# display.net
KiCad netlist of a schematic drawn in EAGLE
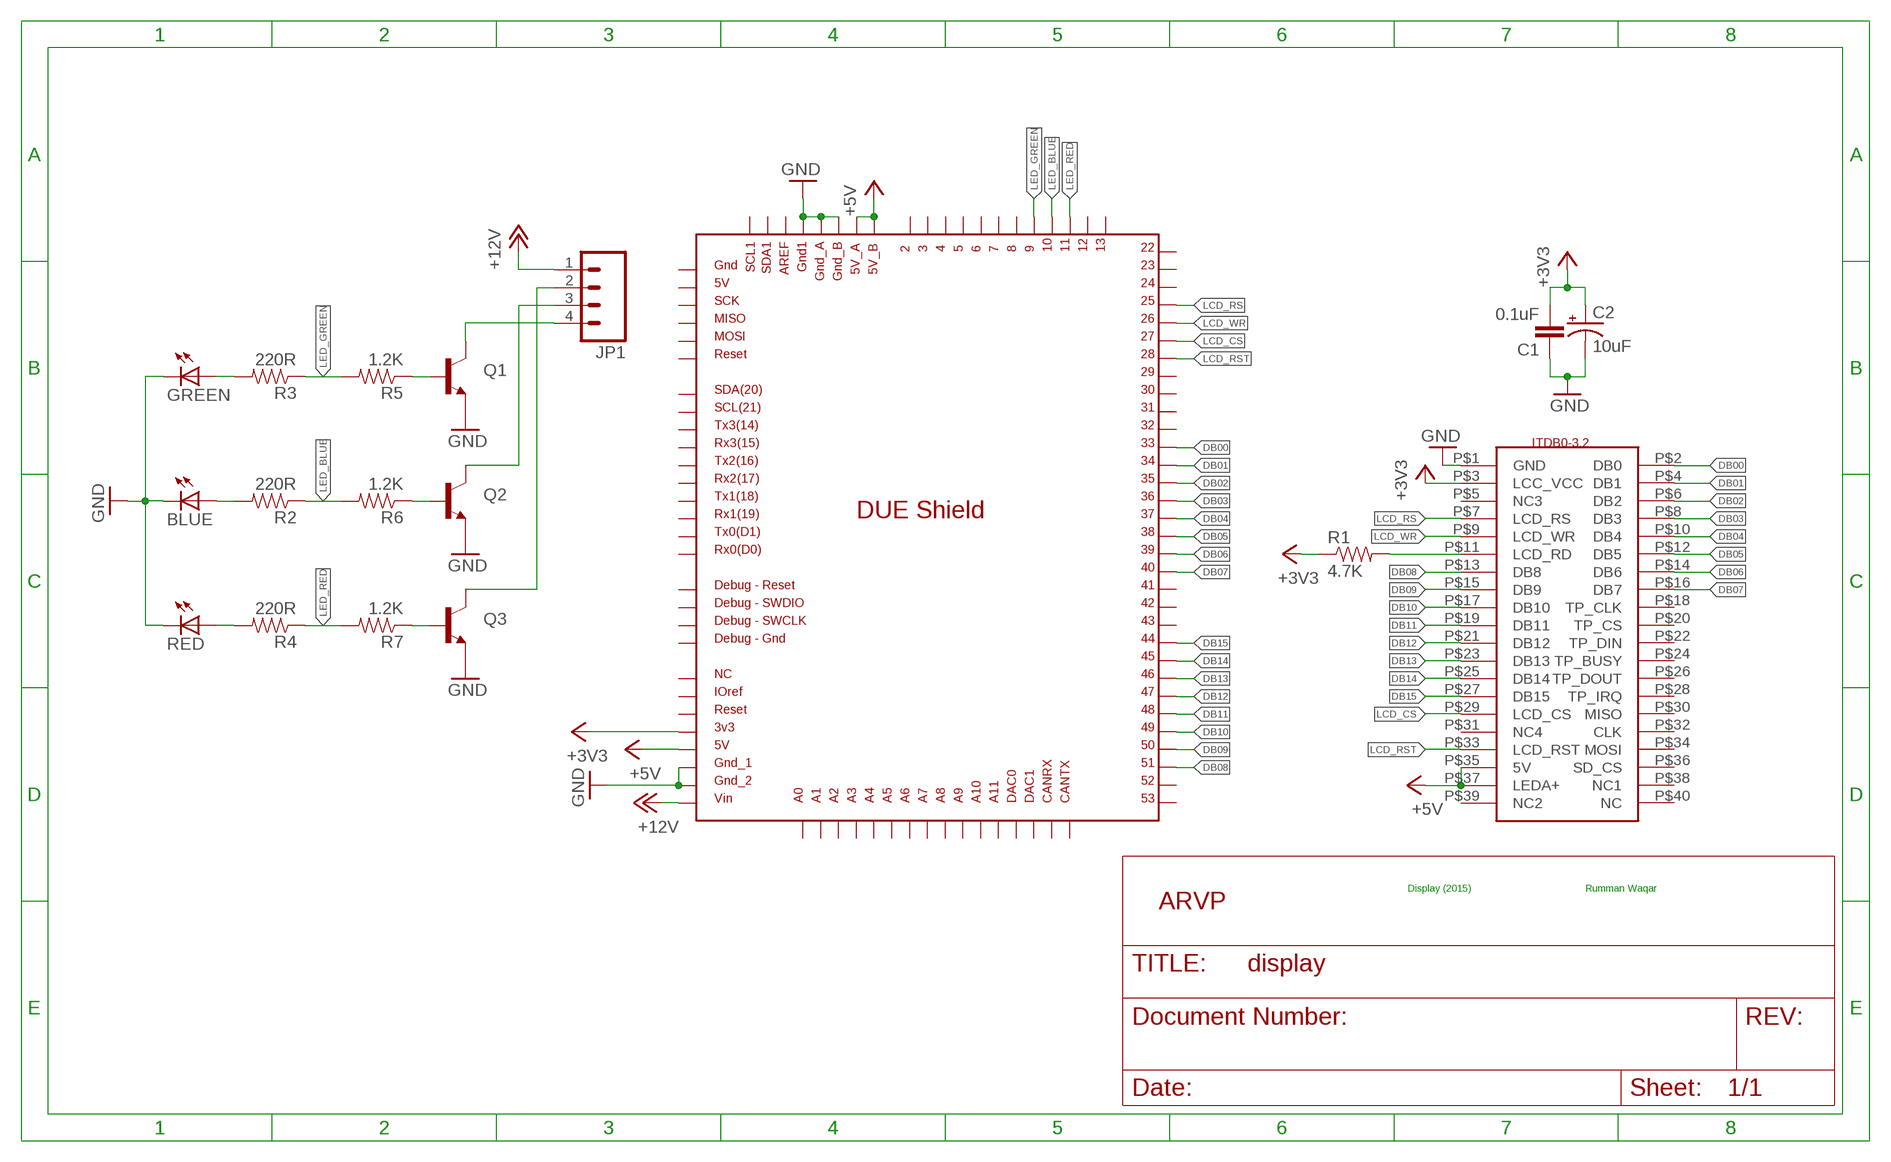
[diagram p0: schematic, sheet 1]

(export (version "E")
  (design (tool "Eeschema 10.0.6"))
  (components
    (comp (ref "BLUE")
      (value "LED1206")
      (footprint "eagle-import:LED-1206")
      (libsource (lib "eagle-import") (part "LED1206"))
    )
    (comp (ref "C1")
      (value "0.1uF")
      (footprint "eagle-import:1206")
      (libsource (lib "eagle-import") (part "CAP1206"))
    )
    (comp (ref "C2")
      (value "10uF")
      (footprint "eagle-import:EIA3216")
      (libsource (lib "eagle-import") (part "CAP_POL1206"))
    )
    (comp (ref "GREEN")
      (value "LED1206")
      (footprint "eagle-import:LED-1206")
      (libsource (lib "eagle-import") (part "LED1206"))
    )
    (comp (ref "JP1")
      (value "M04POLAR")
      (footprint "eagle-import:MOLEX-1X4")
      (libsource (lib "eagle-import") (part "M04POLAR"))
    )
    (comp (ref "Q1")
      (value "TRANSISTOR_NPN\"")
      (footprint "eagle-import:SOT223")
      (libsource (lib "eagle-import") (part "TRANSISTOR_NPN{dblquote}"))
    )
    (comp (ref "Q2")
      (value "TRANSISTOR_NPN\"")
      (footprint "eagle-import:SOT223")
      (libsource (lib "eagle-import") (part "TRANSISTOR_NPN{dblquote}"))
    )
    (comp (ref "Q3")
      (value "TRANSISTOR_NPN\"")
      (footprint "eagle-import:SOT223")
      (libsource (lib "eagle-import") (part "TRANSISTOR_NPN{dblquote}"))
    )
    (comp (ref "R1")
      (value "4.7K")
      (footprint "eagle-import:0805")
      (libsource (lib "eagle-import") (part "RESISTOR0805-RES"))
    )
    (comp (ref "R2")
      (value "220R")
      (footprint "eagle-import:1206")
      (libsource (lib "eagle-import") (part "RESISTOR1206"))
    )
    (comp (ref "R3")
      (value "220R")
      (footprint "eagle-import:1206")
      (libsource (lib "eagle-import") (part "RESISTOR1206"))
    )
    (comp (ref "R4")
      (value "220R")
      (footprint "eagle-import:1206")
      (libsource (lib "eagle-import") (part "RESISTOR1206"))
    )
    (comp (ref "R5")
      (value "1.2K")
      (footprint "eagle-import:1206")
      (libsource (lib "eagle-import") (part "RESISTOR1206"))
    )
    (comp (ref "R6")
      (value "1.2K")
      (footprint "eagle-import:1206")
      (libsource (lib "eagle-import") (part "RESISTOR1206"))
    )
    (comp (ref "R7")
      (value "1.2K")
      (footprint "eagle-import:1206")
      (libsource (lib "eagle-import") (part "RESISTOR1206"))
    )
    (comp (ref "RED")
      (value "LED1206")
      (footprint "eagle-import:LED-1206")
      (libsource (lib "eagle-import") (part "LED1206"))
    )
    (comp (ref "U$1")
      (value "DUE(NORMAL)")
      (footprint "eagle-import:DUE(NORMAL)")
      (libsource (lib "eagle-import") (part "DUE(NORMAL)"))
    )
    (comp (ref "U$2")
      (value "ARVP_LOGO")
      (footprint "eagle-import:ARVP")
      (libsource (lib "eagle-import") (part "ARVP_LOGO"))
    )
    (comp (ref "U$3")
      (value "ITDB0-3.2")
      (footprint "eagle-import:ITDB02-3.2")
      (libsource (lib "eagle-import") (part "ITDB0-3.2"))
    )
  )
  (nets
    (net (code "1") (name "+3V3") (class "Default")
      (node (ref "C1") (pin "2") (pinfunction "2_2") (pintype "passive"))
      (node (ref "C2") (pin "A") (pinfunction "+_A") (pintype "passive"))
      (node (ref "R1") (pin "1") (pinfunction "1_1") (pintype "passive"))
      (node (ref "U$1") (pin "3V3") (pinfunction "3V3_3V3") (pintype "bidirectional"))
      (node (ref "U$3") (pin "P$3") (pinfunction "LCC_VCC_P$3") (pintype "power_in"))
    )
    (net (code "2") (name "+5V") (class "Default")
      (node (ref "U$1") (pin "5V") (pinfunction "5V_5V") (pintype "bidirectional"))
      (node (ref "U$1") (pin "5V_A") (pinfunction "5V_A_5V_A") (pintype "bidirectional"))
      (node (ref "U$1") (pin "5V_B") (pinfunction "5V_B_5V_B") (pintype "bidirectional"))
      (node (ref "U$3") (pin "P$35") (pinfunction "5V_P$35") (pintype "power_in"))
      (node (ref "U$3") (pin "P$37") (pinfunction "LEDA+_P$37") (pintype "power_in"))
    )
    (net (code "3") (name "+12V") (class "Default")
      (node (ref "JP1") (pin "1") (pinfunction "1_1") (pintype "passive"))
      (node (ref "U$1") (pin "VIN") (pinfunction "VIN_VIN") (pintype "bidirectional"))
    )
    (net (code "4") (name "DB00") (class "Default")
      (node (ref "U$1") (pin "33") (pinfunction "33_33") (pintype "bidirectional"))
      (node (ref "U$3") (pin "P$2") (pinfunction "DB0_P$2") (pintype "bidirectional"))
    )
    (net (code "5") (name "DB01") (class "Default")
      (node (ref "U$1") (pin "34") (pinfunction "34_34") (pintype "bidirectional"))
      (node (ref "U$3") (pin "P$4") (pinfunction "DB1_P$4") (pintype "bidirectional"))
    )
    (net (code "6") (name "DB02") (class "Default")
      (node (ref "U$1") (pin "35") (pinfunction "35_35") (pintype "bidirectional"))
      (node (ref "U$3") (pin "P$6") (pinfunction "DB2_P$6") (pintype "bidirectional"))
    )
    (net (code "7") (name "DB03") (class "Default")
      (node (ref "U$1") (pin "36") (pinfunction "36_36") (pintype "bidirectional"))
      (node (ref "U$3") (pin "P$8") (pinfunction "DB3_P$8") (pintype "bidirectional"))
    )
    (net (code "8") (name "DB04") (class "Default")
      (node (ref "U$1") (pin "37") (pinfunction "37_37") (pintype "bidirectional"))
      (node (ref "U$3") (pin "P$10") (pinfunction "DB4_P$10") (pintype "bidirectional"))
    )
    (net (code "9") (name "DB05") (class "Default")
      (node (ref "U$1") (pin "38") (pinfunction "38_38") (pintype "bidirectional"))
      (node (ref "U$3") (pin "P$12") (pinfunction "DB5_P$12") (pintype "bidirectional"))
    )
    (net (code "10") (name "DB06") (class "Default")
      (node (ref "U$1") (pin "39") (pinfunction "39_39") (pintype "bidirectional"))
      (node (ref "U$3") (pin "P$14") (pinfunction "DB6_P$14") (pintype "bidirectional"))
    )
    (net (code "11") (name "DB07") (class "Default")
      (node (ref "U$1") (pin "40") (pinfunction "40_40") (pintype "bidirectional"))
      (node (ref "U$3") (pin "P$16") (pinfunction "DB7_P$16") (pintype "bidirectional"))
    )
    (net (code "12") (name "DB08") (class "Default")
      (node (ref "U$1") (pin "51") (pinfunction "51_51") (pintype "bidirectional"))
      (node (ref "U$3") (pin "P$13") (pinfunction "DB8_P$13") (pintype "bidirectional"))
    )
    (net (code "13") (name "DB09") (class "Default")
      (node (ref "U$1") (pin "50") (pinfunction "50_50") (pintype "bidirectional"))
      (node (ref "U$3") (pin "P$15") (pinfunction "DB9_P$15") (pintype "bidirectional"))
    )
    (net (code "14") (name "DB10") (class "Default")
      (node (ref "U$1") (pin "49") (pinfunction "49_49") (pintype "bidirectional"))
      (node (ref "U$3") (pin "P$17") (pinfunction "DB10_P$17") (pintype "bidirectional"))
    )
    (net (code "15") (name "DB11") (class "Default")
      (node (ref "U$1") (pin "48") (pinfunction "48_48") (pintype "bidirectional"))
      (node (ref "U$3") (pin "P$19") (pinfunction "DB11_P$19") (pintype "bidirectional"))
    )
    (net (code "16") (name "DB12") (class "Default")
      (node (ref "U$1") (pin "47") (pinfunction "47_47") (pintype "bidirectional"))
      (node (ref "U$3") (pin "P$21") (pinfunction "DB12_P$21") (pintype "bidirectional"))
    )
    (net (code "17") (name "DB13") (class "Default")
      (node (ref "U$1") (pin "46") (pinfunction "46_46") (pintype "bidirectional"))
      (node (ref "U$3") (pin "P$23") (pinfunction "DB13_P$23") (pintype "bidirectional"))
    )
    (net (code "18") (name "DB14") (class "Default")
      (node (ref "U$1") (pin "45") (pinfunction "45_45") (pintype "bidirectional"))
      (node (ref "U$3") (pin "P$25") (pinfunction "DB14_P$25") (pintype "bidirectional"))
    )
    (net (code "19") (name "DB15") (class "Default")
      (node (ref "U$1") (pin "44") (pinfunction "44_44") (pintype "bidirectional"))
      (node (ref "U$3") (pin "P$27") (pinfunction "DB15_P$27") (pintype "bidirectional"))
    )
    (net (code "20") (name "GND") (class "Default")
      (node (ref "BLUE") (pin "C") (pinfunction "C_C") (pintype "passive"))
      (node (ref "C1") (pin "1") (pinfunction "1_1") (pintype "passive"))
      (node (ref "C2") (pin "C") (pinfunction "-_C") (pintype "passive"))
      (node (ref "GREEN") (pin "C") (pinfunction "C_C") (pintype "passive"))
      (node (ref "Q1") (pin "3") (pinfunction "E_3") (pintype "passive"))
      (node (ref "Q2") (pin "3") (pinfunction "E_3") (pintype "passive"))
      (node (ref "Q3") (pin "3") (pinfunction "E_3") (pintype "passive"))
      (node (ref "RED") (pin "C") (pinfunction "C_C") (pintype "passive"))
      (node (ref "U$1") (pin "GND1") (pinfunction "GND1_GND1") (pintype "bidirectional"))
      (node (ref "U$1") (pin "GND_1") (pinfunction "GND_1_GND_1") (pintype "bidirectional"))
      (node (ref "U$1") (pin "GND_2") (pinfunction "GND_2_GND_2") (pintype "bidirectional"))
      (node (ref "U$1") (pin "GND_A") (pinfunction "GND_A_GND_A") (pintype "bidirectional"))
      (node (ref "U$1") (pin "GND_B") (pinfunction "GND_B_GND_B") (pintype "bidirectional"))
      (node (ref "U$3") (pin "P$1") (pinfunction "GND_P$1") (pintype "power_in"))
    )
    (net (code "21") (name "LCD_CS") (class "Default")
      (node (ref "U$1") (pin "27") (pinfunction "27_27") (pintype "bidirectional"))
      (node (ref "U$3") (pin "P$29") (pinfunction "LCD_CS_P$29") (pintype "bidirectional"))
    )
    (net (code "22") (name "LCD_RS") (class "Default")
      (node (ref "U$1") (pin "25") (pinfunction "25_25") (pintype "bidirectional"))
      (node (ref "U$3") (pin "P$7") (pinfunction "LCD_RS_P$7") (pintype "bidirectional"))
    )
    (net (code "23") (name "LCD_RST") (class "Default")
      (node (ref "U$1") (pin "28") (pinfunction "28_28") (pintype "bidirectional"))
      (node (ref "U$3") (pin "P$33") (pinfunction "LCD_RST_P$33") (pintype "bidirectional"))
    )
    (net (code "24") (name "LCD_WR") (class "Default")
      (node (ref "U$1") (pin "26") (pinfunction "26_26") (pintype "bidirectional"))
      (node (ref "U$3") (pin "P$9") (pinfunction "LCD_WR_P$9") (pintype "bidirectional"))
    )
    (net (code "25") (name "LED_BLUE") (class "Default")
      (node (ref "R2") (pin "1") (pinfunction "1_1") (pintype "passive"))
      (node (ref "R6") (pin "2") (pinfunction "2_2") (pintype "passive"))
      (node (ref "U$1") (pin "10") (pinfunction "10_10") (pintype "bidirectional"))
    )
    (net (code "26") (name "LED_GREEN") (class "Default")
      (node (ref "R3") (pin "1") (pinfunction "1_1") (pintype "passive"))
      (node (ref "R5") (pin "2") (pinfunction "2_2") (pintype "passive"))
      (node (ref "U$1") (pin "9") (pinfunction "9_9") (pintype "bidirectional"))
    )
    (net (code "27") (name "LED_RED") (class "Default")
      (node (ref "R4") (pin "1") (pinfunction "1_1") (pintype "passive"))
      (node (ref "R7") (pin "2") (pinfunction "2_2") (pintype "passive"))
      (node (ref "U$1") (pin "11") (pinfunction "11_11") (pintype "bidirectional"))
    )
    (net (code "28") (name "Net-(BLUE-PadA)") (class "Default")
      (node (ref "BLUE") (pin "A") (pinfunction "A_A") (pintype "passive"))
      (node (ref "R2") (pin "2") (pinfunction "2_2") (pintype "passive"))
    )
    (net (code "29") (name "Net-(GREEN-PadA)") (class "Default")
      (node (ref "GREEN") (pin "A") (pinfunction "A_A") (pintype "passive"))
      (node (ref "R3") (pin "2") (pinfunction "2_2") (pintype "passive"))
    )
    (net (code "30") (name "Net-(Q1-B)") (class "Default")
      (node (ref "Q1") (pin "1") (pinfunction "B_1") (pintype "passive"))
      (node (ref "R5") (pin "1") (pinfunction "1_1") (pintype "passive"))
    )
    (net (code "31") (name "Net-(Q1-C)") (class "Default")
      (node (ref "JP1") (pin "4") (pinfunction "4_4") (pintype "passive"))
      (node (ref "Q1") (pin "2") (pinfunction "C_2") (pintype "passive"))
    )
    (net (code "32") (name "Net-(Q2-B)") (class "Default")
      (node (ref "Q2") (pin "1") (pinfunction "B_1") (pintype "passive"))
      (node (ref "R6") (pin "1") (pinfunction "1_1") (pintype "passive"))
    )
    (net (code "33") (name "Net-(Q2-C)") (class "Default")
      (node (ref "JP1") (pin "3") (pinfunction "3_3") (pintype "passive"))
      (node (ref "Q2") (pin "2") (pinfunction "C_2") (pintype "passive"))
    )
    (net (code "34") (name "Net-(Q3-B)") (class "Default")
      (node (ref "Q3") (pin "1") (pinfunction "B_1") (pintype "passive"))
      (node (ref "R7") (pin "1") (pinfunction "1_1") (pintype "passive"))
    )
    (net (code "35") (name "Net-(Q3-C)") (class "Default")
      (node (ref "JP1") (pin "2") (pinfunction "2_2") (pintype "passive"))
      (node (ref "Q3") (pin "2") (pinfunction "C_2") (pintype "passive"))
    )
    (net (code "36") (name "Net-(R4-Pad2)") (class "Default")
      (node (ref "R4") (pin "2") (pinfunction "2_2") (pintype "passive"))
      (node (ref "RED") (pin "A") (pinfunction "A_A") (pintype "passive"))
    )
    (net (code "37") (name "Net-(U$3-LCD_RD)") (class "Default")
      (node (ref "R1") (pin "2") (pinfunction "2_2") (pintype "passive"))
      (node (ref "U$3") (pin "P$11") (pinfunction "LCD_RD_P$11") (pintype "bidirectional"))
    )
    (net (code "38") (name "unconnected-(U$1-Pad2)") (class "Default")
      (node (ref "U$1") (pin "2") (pinfunction "2_2") (pintype "bidirectional"))
    )
    (net (code "39") (name "unconnected-(U$1-Pad3)") (class "Default")
      (node (ref "U$1") (pin "3") (pinfunction "3_3") (pintype "bidirectional"))
    )
    (net (code "40") (name "unconnected-(U$1-Pad4)") (class "Default")
      (node (ref "U$1") (pin "4") (pinfunction "4_4") (pintype "bidirectional"))
    )
    (net (code "41") (name "unconnected-(U$1-Pad5)") (class "Default")
      (node (ref "U$1") (pin "5") (pinfunction "5_5") (pintype "bidirectional"))
    )
    (net (code "42") (name "unconnected-(U$1-Pad5V_ICSP)") (class "Default")
      (node (ref "U$1") (pin "5V_ICSP") (pinfunction "5V_ICSP_5V_ICSP") (pintype "bidirectional"))
    )
    (net (code "43") (name "unconnected-(U$1-Pad6)") (class "Default")
      (node (ref "U$1") (pin "6") (pinfunction "6_6") (pintype "bidirectional"))
    )
    (net (code "44") (name "unconnected-(U$1-Pad7)") (class "Default")
      (node (ref "U$1") (pin "7") (pinfunction "7_7") (pintype "bidirectional"))
    )
    (net (code "45") (name "unconnected-(U$1-Pad8)") (class "Default")
      (node (ref "U$1") (pin "8") (pinfunction "8_8") (pintype "bidirectional"))
    )
    (net (code "46") (name "unconnected-(U$1-Pad12)") (class "Default")
      (node (ref "U$1") (pin "12") (pinfunction "12_12") (pintype "bidirectional"))
    )
    (net (code "47") (name "unconnected-(U$1-Pad13)") (class "Default")
      (node (ref "U$1") (pin "13") (pinfunction "13_13") (pintype "bidirectional"))
    )
    (net (code "48") (name "unconnected-(U$1-Pad22)") (class "Default")
      (node (ref "U$1") (pin "22") (pinfunction "22_22") (pintype "bidirectional"))
    )
    (net (code "49") (name "unconnected-(U$1-Pad23)") (class "Default")
      (node (ref "U$1") (pin "23") (pinfunction "23_23") (pintype "bidirectional"))
    )
    (net (code "50") (name "unconnected-(U$1-Pad24)") (class "Default")
      (node (ref "U$1") (pin "24") (pinfunction "24_24") (pintype "bidirectional"))
    )
    (net (code "51") (name "unconnected-(U$1-Pad29)") (class "Default")
      (node (ref "U$1") (pin "29") (pinfunction "29_29") (pintype "bidirectional"))
    )
    (net (code "52") (name "unconnected-(U$1-Pad30)") (class "Default")
      (node (ref "U$1") (pin "30") (pinfunction "30_30") (pintype "bidirectional"))
    )
    (net (code "53") (name "unconnected-(U$1-Pad31)") (class "Default")
      (node (ref "U$1") (pin "31") (pinfunction "31_31") (pintype "bidirectional"))
    )
    (net (code "54") (name "unconnected-(U$1-Pad32)") (class "Default")
      (node (ref "U$1") (pin "32") (pinfunction "32_32") (pintype "bidirectional"))
    )
    (net (code "55") (name "unconnected-(U$1-Pad41)") (class "Default")
      (node (ref "U$1") (pin "41") (pinfunction "41_41") (pintype "bidirectional"))
    )
    (net (code "56") (name "unconnected-(U$1-Pad42)") (class "Default")
      (node (ref "U$1") (pin "42") (pinfunction "42_42") (pintype "bidirectional"))
    )
    (net (code "57") (name "unconnected-(U$1-Pad43)") (class "Default")
      (node (ref "U$1") (pin "43") (pinfunction "43_43") (pintype "bidirectional"))
    )
    (net (code "58") (name "unconnected-(U$1-Pad52)") (class "Default")
      (node (ref "U$1") (pin "52") (pinfunction "52_52") (pintype "bidirectional"))
    )
    (net (code "59") (name "unconnected-(U$1-Pad53)") (class "Default")
      (node (ref "U$1") (pin "53") (pinfunction "53_53") (pintype "bidirectional"))
    )
    (net (code "60") (name "unconnected-(U$1-PadA0)") (class "Default")
      (node (ref "U$1") (pin "A0") (pinfunction "A0_A0") (pintype "bidirectional"))
    )
    (net (code "61") (name "unconnected-(U$1-PadA1)") (class "Default")
      (node (ref "U$1") (pin "A1") (pinfunction "A1_A1") (pintype "bidirectional"))
    )
    (net (code "62") (name "unconnected-(U$1-PadA2)") (class "Default")
      (node (ref "U$1") (pin "A2") (pinfunction "A2_A2") (pintype "bidirectional"))
    )
    (net (code "63") (name "unconnected-(U$1-PadA3)") (class "Default")
      (node (ref "U$1") (pin "A3") (pinfunction "A3_A3") (pintype "bidirectional"))
    )
    (net (code "64") (name "unconnected-(U$1-PadA4)") (class "Default")
      (node (ref "U$1") (pin "A4") (pinfunction "A4_A4") (pintype "bidirectional"))
    )
    (net (code "65") (name "unconnected-(U$1-PadA5)") (class "Default")
      (node (ref "U$1") (pin "A5") (pinfunction "A5_A5") (pintype "bidirectional"))
    )
    (net (code "66") (name "unconnected-(U$1-PadA6)") (class "Default")
      (node (ref "U$1") (pin "A6") (pinfunction "A6_A6") (pintype "bidirectional"))
    )
    (net (code "67") (name "unconnected-(U$1-PadA7)") (class "Default")
      (node (ref "U$1") (pin "A7") (pinfunction "A7_A7") (pintype "bidirectional"))
    )
    (net (code "68") (name "unconnected-(U$1-PadA8)") (class "Default")
      (node (ref "U$1") (pin "A8") (pinfunction "A8_A8") (pintype "bidirectional"))
    )
    (net (code "69") (name "unconnected-(U$1-PadA9)") (class "Default")
      (node (ref "U$1") (pin "A9") (pinfunction "A9_A9") (pintype "bidirectional"))
    )
    (net (code "70") (name "unconnected-(U$1-PadA10)") (class "Default")
      (node (ref "U$1") (pin "A10") (pinfunction "A10_A10") (pintype "bidirectional"))
    )
    (net (code "71") (name "unconnected-(U$1-PadA11)") (class "Default")
      (node (ref "U$1") (pin "A11") (pinfunction "A11_A11") (pintype "bidirectional"))
    )
    (net (code "72") (name "unconnected-(U$1-PadAREF)") (class "Default")
      (node (ref "U$1") (pin "AREF") (pinfunction "AREF_AREF") (pintype "bidirectional"))
    )
    (net (code "73") (name "unconnected-(U$1-PadCANRX)") (class "Default")
      (node (ref "U$1") (pin "CANRX") (pinfunction "CANRX_CANRX") (pintype "bidirectional"))
    )
    (net (code "74") (name "unconnected-(U$1-PadCANTX)") (class "Default")
      (node (ref "U$1") (pin "CANTX") (pinfunction "CANTX_CANTX") (pintype "bidirectional"))
    )
    (net (code "75") (name "unconnected-(U$1-PadDAC0)") (class "Default")
      (node (ref "U$1") (pin "DAC0") (pinfunction "DAC0_DAC0") (pintype "bidirectional"))
    )
    (net (code "76") (name "unconnected-(U$1-PadDAC1)") (class "Default")
      (node (ref "U$1") (pin "DAC1") (pinfunction "DAC1_DAC1") (pintype "bidirectional"))
    )
    (net (code "77") (name "unconnected-(U$1-PadGND_DEBUG)") (class "Default")
      (node (ref "U$1") (pin "GND_DEBUG") (pinfunction "GND_DEBUG_GND_DEBUG") (pintype "bidirectional"))
    )
    (net (code "78") (name "unconnected-(U$1-PadGND_ICSP)") (class "Default")
      (node (ref "U$1") (pin "GND_ICSP") (pinfunction "GND_ICSP_GND_ICSP") (pintype "bidirectional"))
    )
    (net (code "79") (name "unconnected-(U$1-PadIOREF)") (class "Default")
      (node (ref "U$1") (pin "IOREF") (pinfunction "IOREF_IOREF") (pintype "bidirectional"))
    )
    (net (code "80") (name "unconnected-(U$1-PadMISO_ICSP)") (class "Default")
      (node (ref "U$1") (pin "MISO_ICSP") (pinfunction "MISO_ICSP_MISO_ICSP") (pintype "bidirectional"))
    )
    (net (code "81") (name "unconnected-(U$1-PadMOSI_ICSP)") (class "Default")
      (node (ref "U$1") (pin "MOSI_ICSP") (pinfunction "MOSI_ICSP_MOSI_ICSP") (pintype "bidirectional"))
    )
    (net (code "82") (name "unconnected-(U$1-PadNC)") (class "Default")
      (node (ref "U$1") (pin "NC") (pinfunction "NC_NC") (pintype "bidirectional"))
    )
    (net (code "83") (name "unconnected-(U$1-PadRESET)") (class "Default")
      (node (ref "U$1") (pin "RESET") (pinfunction "RESET_RESET") (pintype "bidirectional"))
    )
    (net (code "84") (name "unconnected-(U$1-PadRESET_DEBUG)") (class "Default")
      (node (ref "U$1") (pin "RESET_DEBUG") (pinfunction "RESET_DEBUG_RESET_DEBUG") (pintype "bidirectional"))
    )
    (net (code "85") (name "unconnected-(U$1-PadRESET_ICSP)") (class "Default")
      (node (ref "U$1") (pin "RESET_ICSP") (pinfunction "RESET_ICSP_RESET_ICSP") (pintype "bidirectional"))
    )
    (net (code "86") (name "unconnected-(U$1-PadRX0)") (class "Default")
      (node (ref "U$1") (pin "RX0") (pinfunction "RX0_RX0") (pintype "bidirectional"))
    )
    (net (code "87") (name "unconnected-(U$1-PadRX1)") (class "Default")
      (node (ref "U$1") (pin "RX1") (pinfunction "RX1_RX1") (pintype "bidirectional"))
    )
    (net (code "88") (name "unconnected-(U$1-PadRX2)") (class "Default")
      (node (ref "U$1") (pin "RX2") (pinfunction "RX2_RX2") (pintype "bidirectional"))
    )
    (net (code "89") (name "unconnected-(U$1-PadRX3)") (class "Default")
      (node (ref "U$1") (pin "RX3") (pinfunction "RX3_RX3") (pintype "bidirectional"))
    )
    (net (code "90") (name "unconnected-(U$1-PadSCK_ICSP)") (class "Default")
      (node (ref "U$1") (pin "SCK_ICSP") (pinfunction "SCK_ICSP_SCK_ICSP") (pintype "bidirectional"))
    )
    (net (code "91") (name "unconnected-(U$1-PadSCL)") (class "Default")
      (node (ref "U$1") (pin "SCL") (pinfunction "SCL_SCL") (pintype "bidirectional"))
    )
    (net (code "92") (name "unconnected-(U$1-PadSCL1)") (class "Default")
      (node (ref "U$1") (pin "SCL1") (pinfunction "SCL1_SCL1") (pintype "bidirectional"))
    )
    (net (code "93") (name "unconnected-(U$1-PadSDA)") (class "Default")
      (node (ref "U$1") (pin "SDA") (pinfunction "SDA_SDA") (pintype "bidirectional"))
    )
    (net (code "94") (name "unconnected-(U$1-PadSDA1)") (class "Default")
      (node (ref "U$1") (pin "SDA1") (pinfunction "SDA1_SDA1") (pintype "bidirectional"))
    )
    (net (code "95") (name "unconnected-(U$1-PadSWCLK_DEBUG)") (class "Default")
      (node (ref "U$1") (pin "SWCLK_DEBUG") (pinfunction "SWCLK_DEBUG_SWCLK_DEBUG") (pintype "bidirectional"))
    )
    (net (code "96") (name "unconnected-(U$1-PadSWDIO_DEBUG)") (class "Default")
      (node (ref "U$1") (pin "SWDIO_DEBUG") (pinfunction "SWDIO_DEBUG_SWDIO_DEBUG") (pintype "bidirectional"))
    )
    (net (code "97") (name "unconnected-(U$1-PadTX0)") (class "Default")
      (node (ref "U$1") (pin "TX0") (pinfunction "TX0_TX0") (pintype "bidirectional"))
    )
    (net (code "98") (name "unconnected-(U$1-PadTX1)") (class "Default")
      (node (ref "U$1") (pin "TX1") (pinfunction "TX1_TX1") (pintype "bidirectional"))
    )
    (net (code "99") (name "unconnected-(U$1-PadTX2)") (class "Default")
      (node (ref "U$1") (pin "TX2") (pinfunction "TX2_TX2") (pintype "bidirectional"))
    )
    (net (code "100") (name "unconnected-(U$1-PadTX3)") (class "Default")
      (node (ref "U$1") (pin "TX3") (pinfunction "TX3_TX3") (pintype "bidirectional"))
    )
    (net (code "101") (name "unconnected-(U$3-CLK-PadP$32)") (class "Default")
      (node (ref "U$3") (pin "P$32") (pinfunction "CLK_P$32") (pintype "bidirectional"))
    )
    (net (code "102") (name "unconnected-(U$3-MISO-PadP$30)") (class "Default")
      (node (ref "U$3") (pin "P$30") (pinfunction "MISO_P$30") (pintype "bidirectional"))
    )
    (net (code "103") (name "unconnected-(U$3-MOSI-PadP$34)") (class "Default")
      (node (ref "U$3") (pin "P$34") (pinfunction "MOSI_P$34") (pintype "bidirectional"))
    )
    (net (code "104") (name "unconnected-(U$3-NC-PadP$40)") (class "Default")
      (node (ref "U$3") (pin "P$40") (pinfunction "NC_P$40") (pintype "no_connect"))
    )
    (net (code "105") (name "unconnected-(U$3-NC1-PadP$38)") (class "Default")
      (node (ref "U$3") (pin "P$38") (pinfunction "NC1_P$38") (pintype "no_connect"))
    )
    (net (code "106") (name "unconnected-(U$3-NC2-PadP$39)") (class "Default")
      (node (ref "U$3") (pin "P$39") (pinfunction "NC2_P$39") (pintype "no_connect"))
    )
    (net (code "107") (name "unconnected-(U$3-NC3-PadP$5)") (class "Default")
      (node (ref "U$3") (pin "P$5") (pinfunction "NC3_P$5") (pintype "no_connect"))
    )
    (net (code "108") (name "unconnected-(U$3-NC4-PadP$31)") (class "Default")
      (node (ref "U$3") (pin "P$31") (pinfunction "NC4_P$31") (pintype "no_connect"))
    )
    (net (code "109") (name "unconnected-(U$3-SD_CS-PadP$36)") (class "Default")
      (node (ref "U$3") (pin "P$36") (pinfunction "SD_CS_P$36") (pintype "bidirectional"))
    )
    (net (code "110") (name "unconnected-(U$3-TP_BUSY-PadP$24)") (class "Default")
      (node (ref "U$3") (pin "P$24") (pinfunction "TP_BUSY_P$24") (pintype "bidirectional"))
    )
    (net (code "111") (name "unconnected-(U$3-TP_CLK-PadP$18)") (class "Default")
      (node (ref "U$3") (pin "P$18") (pinfunction "TP_CLK_P$18") (pintype "bidirectional"))
    )
    (net (code "112") (name "unconnected-(U$3-TP_CS-PadP$20)") (class "Default")
      (node (ref "U$3") (pin "P$20") (pinfunction "TP_CS_P$20") (pintype "bidirectional"))
    )
    (net (code "113") (name "unconnected-(U$3-TP_DIN-PadP$22)") (class "Default")
      (node (ref "U$3") (pin "P$22") (pinfunction "TP_DIN_P$22") (pintype "bidirectional"))
    )
    (net (code "114") (name "unconnected-(U$3-TP_DOUT-PadP$26)") (class "Default")
      (node (ref "U$3") (pin "P$26") (pinfunction "TP_DOUT_P$26") (pintype "bidirectional"))
    )
    (net (code "115") (name "unconnected-(U$3-TP_IRQ-PadP$28)") (class "Default")
      (node (ref "U$3") (pin "P$28") (pinfunction "TP_IRQ_P$28") (pintype "bidirectional"))
    )
  )
)
